# source_eagle.net
KiCad netlist of a schematic drawn in EAGLE
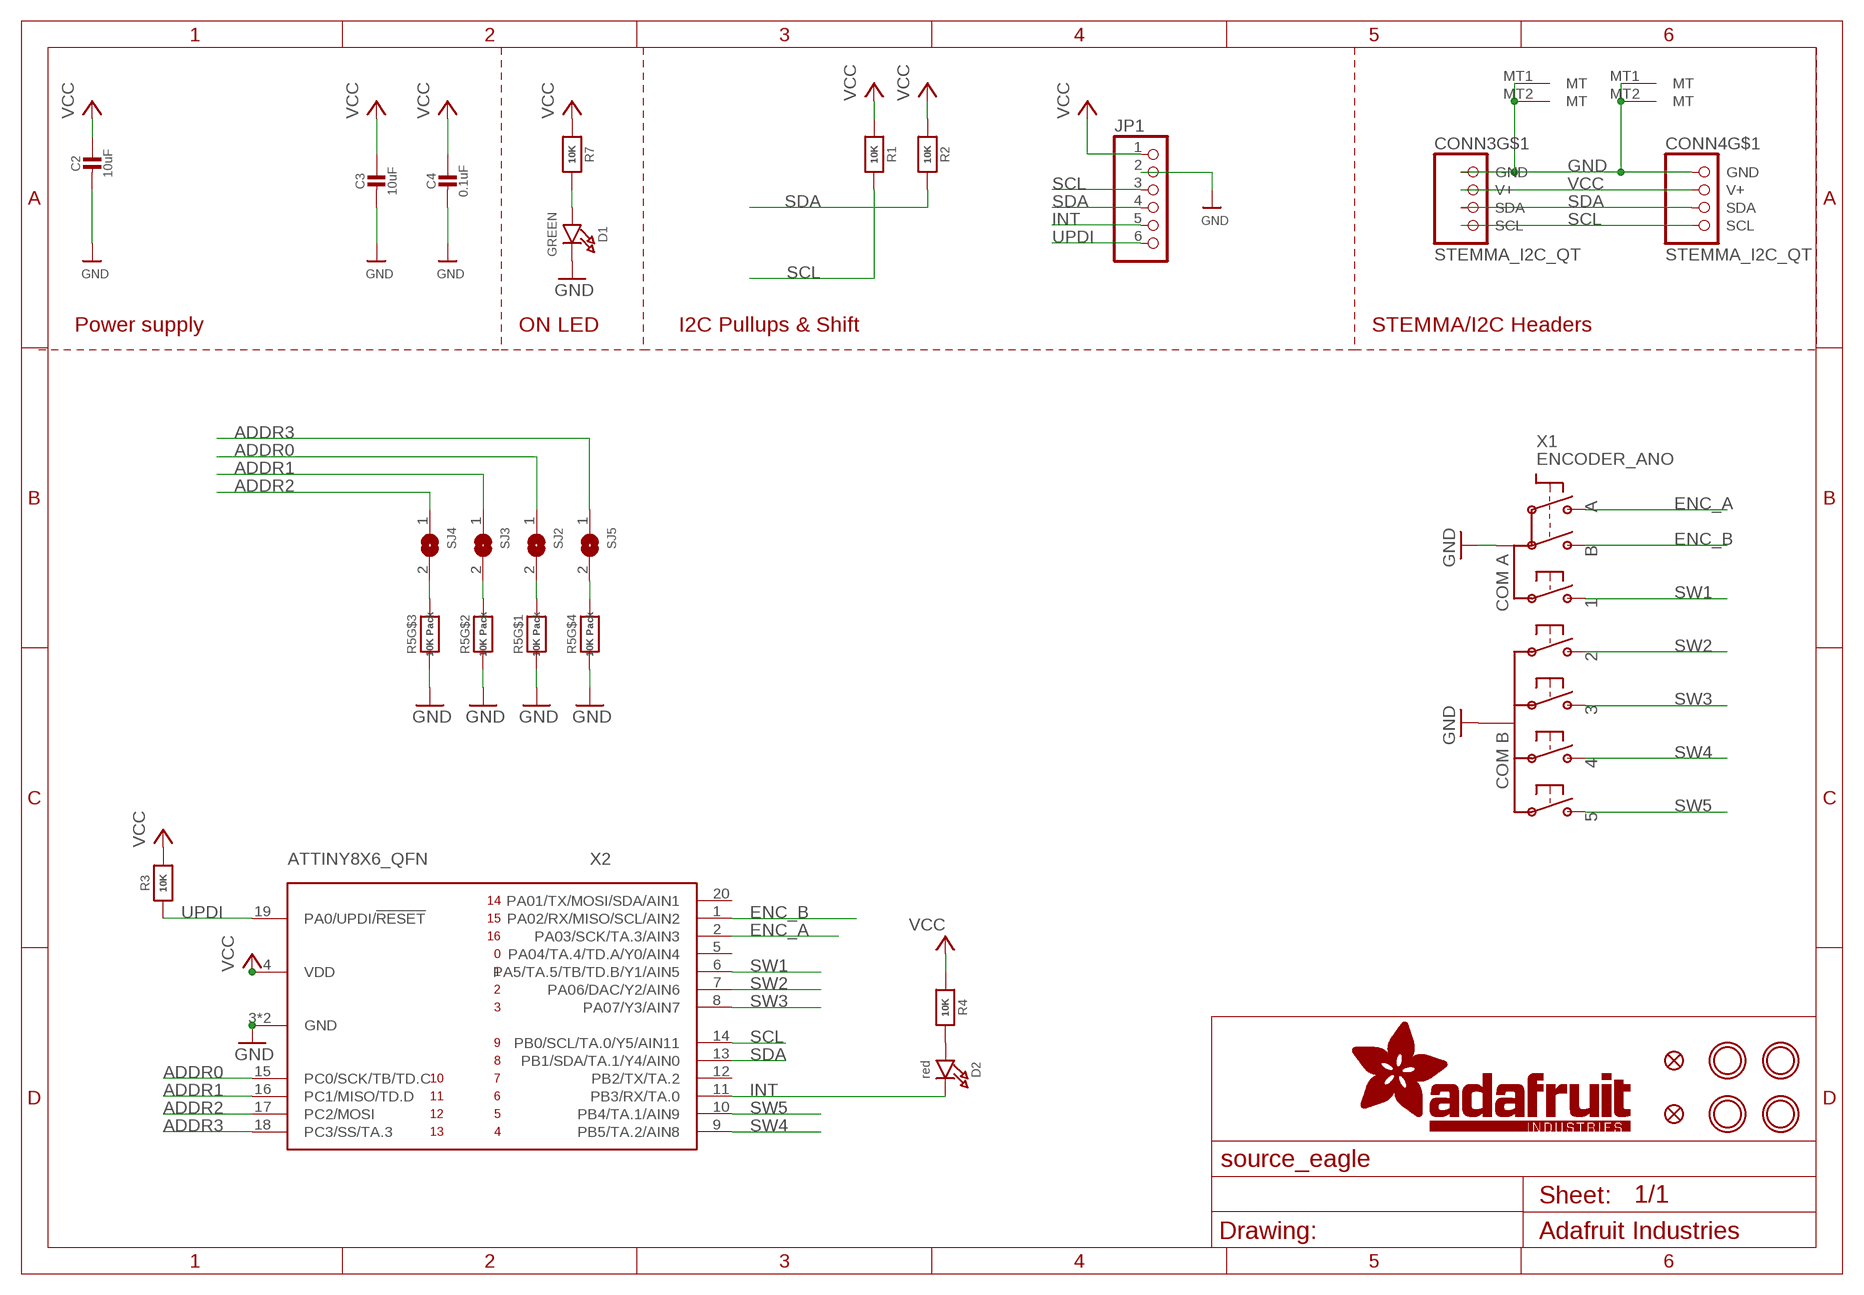
[diagram p0: schematic, sheet 1]

(export (version "E")
  (design (tool "Eeschema 10.0.6"))
  (components
    (comp (ref "C2")
      (value "10uF")
      (footprint "eagle-import:0805-NO")
      (libsource (lib "eagle-import") (part "CAP_CERAMIC0805-NOOUTLINE"))
    )
    (comp (ref "C3")
      (value "10uF")
      (footprint "eagle-import:0805-NO")
      (libsource (lib "eagle-import") (part "CAP_CERAMIC0805-NOOUTLINE"))
    )
    (comp (ref "C4")
      (value "0.1uF")
      (footprint "eagle-import:0603-NO")
      (libsource (lib "eagle-import") (part "CAP_CERAMIC0603_NO"))
    )
    (comp (ref "CONN3")
      (value "STEMMA_I2C_QT")
      (footprint "eagle-import:JST_SH4")
      (libsource (lib "eagle-import") (part "STEMMA_I2C_QT"))
    )
    (comp (ref "CONN4")
      (value "STEMMA_I2C_QT")
      (footprint "eagle-import:JST_SH4")
      (libsource (lib "eagle-import") (part "STEMMA_I2C_QT"))
    )
    (comp (ref "D1")
      (value "GREEN")
      (footprint "eagle-import:CHIPLED_0603_NOOUTLINE")
      (libsource (lib "eagle-import") (part "LED0603_NOOUTLINE"))
    )
    (comp (ref "D2")
      (value "red")
      (footprint "eagle-import:CHIPLED_0603_NOOUTLINE")
      (libsource (lib "eagle-import") (part "LED0603_NOOUTLINE"))
    )
    (comp (ref "FID3")
      (value "FIDUCIAL_1MM")
      (footprint "eagle-import:FIDUCIAL_1MM")
      (libsource (lib "eagle-import") (part "FIDUCIAL_1MM"))
    )
    (comp (ref "FID4")
      (value "FIDUCIAL_1MM")
      (footprint "eagle-import:FIDUCIAL_1MM")
      (libsource (lib "eagle-import") (part "FIDUCIAL_1MM"))
    )
    (comp (ref "JP1")
      (value "HEADER-1X670MIL")
      (footprint "eagle-import:1X06_ROUND_70")
      (libsource (lib "eagle-import") (part "HEADER-1X670MIL"))
    )
    (comp (ref "R1")
      (value "10K")
      (footprint "eagle-import:0603-NO")
      (libsource (lib "eagle-import") (part "RESISTOR_0603_NOOUT"))
    )
    (comp (ref "R2")
      (value "10K")
      (footprint "eagle-import:0603-NO")
      (libsource (lib "eagle-import") (part "RESISTOR_0603_NOOUT"))
    )
    (comp (ref "R3")
      (value "10K")
      (footprint "eagle-import:0603-NO")
      (libsource (lib "eagle-import") (part "RESISTOR_0603_NOOUT"))
    )
    (comp (ref "R4")
      (value "10K")
      (footprint "eagle-import:0603-NO")
      (libsource (lib "eagle-import") (part "RESISTOR_0603_NOOUT"))
    )
    (comp (ref "R5")
      (value "10K Pack")
      (footprint "eagle-import:RESPACK_4X0603")
      (libsource (lib "eagle-import") (part "RESISTOR_4PACK"))
    )
    (comp (ref "R7")
      (value "10K")
      (footprint "eagle-import:0603-NO")
      (libsource (lib "eagle-import") (part "RESISTOR_0603_NOOUT"))
    )
    (comp (ref "SJ2")
      (value "SOLDERJUMPERCLOSED")
      (footprint "eagle-import:SOLDERJUMPER_CLOSEDWIRE")
      (libsource (lib "eagle-import") (part "SOLDERJUMPERCLOSED"))
    )
    (comp (ref "SJ3")
      (value "SOLDERJUMPERCLOSED")
      (footprint "eagle-import:SOLDERJUMPER_CLOSEDWIRE")
      (libsource (lib "eagle-import") (part "SOLDERJUMPERCLOSED"))
    )
    (comp (ref "SJ4")
      (value "SOLDERJUMPERCLOSED")
      (footprint "eagle-import:SOLDERJUMPER_CLOSEDWIRE")
      (libsource (lib "eagle-import") (part "SOLDERJUMPERCLOSED"))
    )
    (comp (ref "SJ5")
      (value "SOLDERJUMPERCLOSED")
      (footprint "eagle-import:SOLDERJUMPER_CLOSEDWIRE")
      (libsource (lib "eagle-import") (part "SOLDERJUMPERCLOSED"))
    )
    (comp (ref "U$25")
      (value "MOUNTINGHOLE2.5")
      (footprint "eagle-import:MOUNTINGHOLE_2.5_PLATED")
      (libsource (lib "eagle-import") (part "MOUNTINGHOLE2.5"))
    )
    (comp (ref "U$27")
      (value "MOUNTINGHOLE2.5")
      (footprint "eagle-import:MOUNTINGHOLE_2.5_PLATED")
      (libsource (lib "eagle-import") (part "MOUNTINGHOLE2.5"))
    )
    (comp (ref "U$29")
      (value "MOUNTINGHOLE2.5")
      (footprint "eagle-import:MOUNTINGHOLE_2.5_PLATED")
      (libsource (lib "eagle-import") (part "MOUNTINGHOLE2.5"))
    )
    (comp (ref "U$30")
      (value "MOUNTINGHOLE2.5")
      (footprint "eagle-import:MOUNTINGHOLE_2.5_PLATED")
      (libsource (lib "eagle-import") (part "MOUNTINGHOLE2.5"))
    )
    (comp (ref "X1")
      (value "ENCODER_ANO")
      (footprint "eagle-import:ENCODER_ANO")
      (libsource (lib "eagle-import") (part "ENCODER_ANO"))
    )
    (comp (ref "X2")
      (value "ATTINY8X6_QFN")
      (footprint "eagle-import:QFN20_3MM")
      (libsource (lib "eagle-import") (part "ATTINY8X6_QFN"))
    )
  )
  (nets
    (net (code "1") (name "/ADDR0") (class "Default")
      (node (ref "SJ2") (pin "1") (pinfunction "1_1") (pintype "passive"))
      (node (ref "X2") (pin "15") (pinfunction "PC0/SCK/TB/TD.C_15") (pintype "bidirectional"))
    )
    (net (code "2") (name "/ADDR1") (class "Default")
      (node (ref "SJ3") (pin "1") (pinfunction "1_1") (pintype "passive"))
      (node (ref "X2") (pin "16") (pinfunction "PC1/MISO/TD.D_16") (pintype "bidirectional"))
    )
    (net (code "3") (name "/ADDR2") (class "Default")
      (node (ref "SJ4") (pin "1") (pinfunction "1_1") (pintype "passive"))
      (node (ref "X2") (pin "17") (pinfunction "PC2/MOSI_17") (pintype "bidirectional"))
    )
    (net (code "4") (name "/ADDR3") (class "Default")
      (node (ref "SJ5") (pin "1") (pinfunction "1_1") (pintype "passive"))
      (node (ref "X2") (pin "18") (pinfunction "PC3/SS/TA.3_18") (pintype "bidirectional"))
    )
    (net (code "5") (name "/ENC_A") (class "Default")
      (node (ref "X1") (pin "A") (pinfunction "A_A") (pintype "passive"))
      (node (ref "X2") (pin "2") (pinfunction "PA03/SCK/TA.3/AIN3_2") (pintype "bidirectional"))
    )
    (net (code "6") (name "/ENC_B") (class "Default")
      (node (ref "X1") (pin "B") (pinfunction "B_B") (pintype "passive"))
      (node (ref "X2") (pin "1") (pinfunction "PA02/RX/MISO/SCL/AIN2_1") (pintype "bidirectional"))
    )
    (net (code "7") (name "/INT") (class "Default")
      (node (ref "D2") (pin "C") (pinfunction "C_C") (pintype "passive"))
      (node (ref "JP1") (pin "5") (pinfunction "5_5") (pintype "passive"))
      (node (ref "X2") (pin "11") (pinfunction "PB3/RX/TA.0_11") (pintype "bidirectional"))
    )
    (net (code "8") (name "/SCL") (class "Default")
      (node (ref "CONN3") (pin "4") (pinfunction "SCL_4") (pintype "passive"))
      (node (ref "CONN4") (pin "4") (pinfunction "SCL_4") (pintype "passive"))
      (node (ref "JP1") (pin "3") (pinfunction "3_3") (pintype "passive"))
      (node (ref "R1") (pin "2") (pinfunction "2_2") (pintype "passive"))
      (node (ref "X2") (pin "14") (pinfunction "PB0/SCL/TA.0/Y5/AIN11_14") (pintype "bidirectional"))
    )
    (net (code "9") (name "/SDA") (class "Default")
      (node (ref "CONN3") (pin "3") (pinfunction "SDA_3") (pintype "passive"))
      (node (ref "CONN4") (pin "3") (pinfunction "SDA_3") (pintype "passive"))
      (node (ref "JP1") (pin "4") (pinfunction "4_4") (pintype "passive"))
      (node (ref "R2") (pin "2") (pinfunction "2_2") (pintype "passive"))
      (node (ref "X2") (pin "13") (pinfunction "PB1/SDA/TA.1/Y4/AIN0_13") (pintype "bidirectional"))
    )
    (net (code "10") (name "/SW1") (class "Default")
      (node (ref "X1") (pin "S1") (pinfunction "1_S1") (pintype "passive"))
      (node (ref "X2") (pin "6") (pinfunction "PA5/TA.5/TB/TD.B/Y1/AIN5_6") (pintype "bidirectional"))
    )
    (net (code "11") (name "/SW2") (class "Default")
      (node (ref "X1") (pin "S2") (pinfunction "S2_S2") (pintype "passive"))
      (node (ref "X2") (pin "7") (pinfunction "PA06/DAC/Y2/AIN6_7") (pintype "bidirectional"))
    )
    (net (code "12") (name "/SW3") (class "Default")
      (node (ref "X1") (pin "S3") (pinfunction "S3_S3") (pintype "passive"))
      (node (ref "X2") (pin "8") (pinfunction "PA07/Y3/AIN7_8") (pintype "bidirectional"))
    )
    (net (code "13") (name "/SW4") (class "Default")
      (node (ref "X1") (pin "S4") (pinfunction "S4_S4") (pintype "passive"))
      (node (ref "X2") (pin "9") (pinfunction "PB5/TA.2/AIN8_9") (pintype "bidirectional"))
    )
    (net (code "14") (name "/SW5") (class "Default")
      (node (ref "X1") (pin "S5") (pinfunction "S5_S5") (pintype "passive"))
      (node (ref "X2") (pin "10") (pinfunction "PB4/TA.1/AIN9_10") (pintype "bidirectional"))
    )
    (net (code "15") (name "/UPDI") (class "Default")
      (node (ref "JP1") (pin "6") (pinfunction "6_6") (pintype "passive"))
      (node (ref "R3") (pin "1") (pinfunction "1_1") (pintype "passive"))
      (node (ref "X2") (pin "19") (pinfunction "PA0/UPDI/~{RESET}_19") (pintype "bidirectional"))
    )
    (net (code "16") (name "GND") (class "Default")
      (node (ref "C2") (pin "2") (pinfunction "2_2") (pintype "passive"))
      (node (ref "C3") (pin "2") (pinfunction "2_2") (pintype "passive"))
      (node (ref "C4") (pin "2") (pinfunction "2_2") (pintype "passive"))
      (node (ref "CONN3") (pin "1") (pinfunction "GND_1") (pintype "passive"))
      (node (ref "CONN3") (pin "MT1") (pinfunction "MT_MT1") (pintype "bidirectional"))
      (node (ref "CONN3") (pin "MT2") (pinfunction "MT_MT2") (pintype "bidirectional"))
      (node (ref "CONN4") (pin "1") (pinfunction "GND_1") (pintype "passive"))
      (node (ref "CONN4") (pin "MT1") (pinfunction "MT_MT1") (pintype "bidirectional"))
      (node (ref "CONN4") (pin "MT2") (pinfunction "MT_MT2") (pintype "bidirectional"))
      (node (ref "D1") (pin "C") (pinfunction "C_C") (pintype "passive"))
      (node (ref "JP1") (pin "2") (pinfunction "2_2") (pintype "passive"))
      (node (ref "R5") (pin "1") (pinfunction "1_1") (pintype "passive"))
      (node (ref "R5") (pin "2") (pinfunction "1_2") (pintype "passive"))
      (node (ref "R5") (pin "3") (pinfunction "1_3") (pintype "passive"))
      (node (ref "R5") (pin "4") (pinfunction "1_4") (pintype "passive"))
      (node (ref "X1") (pin "COM_A") (pinfunction "COMA_COM_A") (pintype "passive"))
      (node (ref "X1") (pin "COM_B") (pinfunction "COM_B_COM_B") (pintype "passive"))
      (node (ref "X2") (pin "3") (pinfunction "GND_3") (pintype "power_in"))
      (node (ref "X2") (pin "PAD") (pinfunction "GND_PAD") (pintype "power_in"))
    )
    (net (code "17") (name "Net-(D1-PadA)") (class "Default")
      (node (ref "D1") (pin "A") (pinfunction "A_A") (pintype "passive"))
      (node (ref "R7") (pin "2") (pinfunction "2_2") (pintype "passive"))
    )
    (net (code "18") (name "Net-(D2-PadA)") (class "Default")
      (node (ref "D2") (pin "A") (pinfunction "A_A") (pintype "passive"))
      (node (ref "R4") (pin "2") (pinfunction "2_2") (pintype "passive"))
    )
    (net (code "19") (name "Net-(R5A-2)") (class "Default")
      (node (ref "R5") (pin "8") (pinfunction "2_8") (pintype "passive"))
      (node (ref "SJ2") (pin "2") (pinfunction "2_2") (pintype "passive"))
    )
    (net (code "20") (name "Net-(R5B-2)") (class "Default")
      (node (ref "R5") (pin "7") (pinfunction "2_7") (pintype "passive"))
      (node (ref "SJ3") (pin "2") (pinfunction "2_2") (pintype "passive"))
    )
    (net (code "21") (name "Net-(R5C-2)") (class "Default")
      (node (ref "R5") (pin "6") (pinfunction "2_6") (pintype "passive"))
      (node (ref "SJ4") (pin "2") (pinfunction "2_2") (pintype "passive"))
    )
    (net (code "22") (name "Net-(R5D-2)") (class "Default")
      (node (ref "R5") (pin "5") (pinfunction "2_5") (pintype "passive"))
      (node (ref "SJ5") (pin "2") (pinfunction "2_2") (pintype "passive"))
    )
    (net (code "23") (name "VCC") (class "Default")
      (node (ref "C2") (pin "1") (pinfunction "1_1") (pintype "passive"))
      (node (ref "C3") (pin "1") (pinfunction "1_1") (pintype "passive"))
      (node (ref "C4") (pin "1") (pinfunction "1_1") (pintype "passive"))
      (node (ref "CONN3") (pin "2") (pinfunction "V+_2") (pintype "passive"))
      (node (ref "CONN4") (pin "2") (pinfunction "V+_2") (pintype "passive"))
      (node (ref "JP1") (pin "1") (pinfunction "1_1") (pintype "passive"))
      (node (ref "R1") (pin "1") (pinfunction "1_1") (pintype "passive"))
      (node (ref "R2") (pin "1") (pinfunction "1_1") (pintype "passive"))
      (node (ref "R3") (pin "2") (pinfunction "2_2") (pintype "passive"))
      (node (ref "R4") (pin "1") (pinfunction "1_1") (pintype "passive"))
      (node (ref "R7") (pin "1") (pinfunction "1_1") (pintype "passive"))
      (node (ref "X2") (pin "4") (pinfunction "VDD_4") (pintype "power_in"))
    )
    (net (code "24") (name "unconnected-(X2-PA01{slash}TX{slash}MOSI{slash}SDA{slash}AIN1-Pad20)") (class "Default")
      (node (ref "X2") (pin "20") (pinfunction "PA01/TX/MOSI/SDA/AIN1_20") (pintype "bidirectional"))
    )
    (net (code "25") (name "unconnected-(X2-PA04{slash}TA.4{slash}TD.A{slash}Y0{slash}AIN4-Pad5)") (class "Default")
      (node (ref "X2") (pin "5") (pinfunction "PA04/TA.4/TD.A/Y0/AIN4_5") (pintype "bidirectional"))
    )
    (net (code "26") (name "unconnected-(X2-PB2{slash}TX{slash}TA.2-Pad12)") (class "Default")
      (node (ref "X2") (pin "12") (pinfunction "PB2/TX/TA.2_12") (pintype "bidirectional"))
    )
  )
)
